# Amphenol_ICC_2.net
KiCad netlist of a schematic drawn in Altium Designer
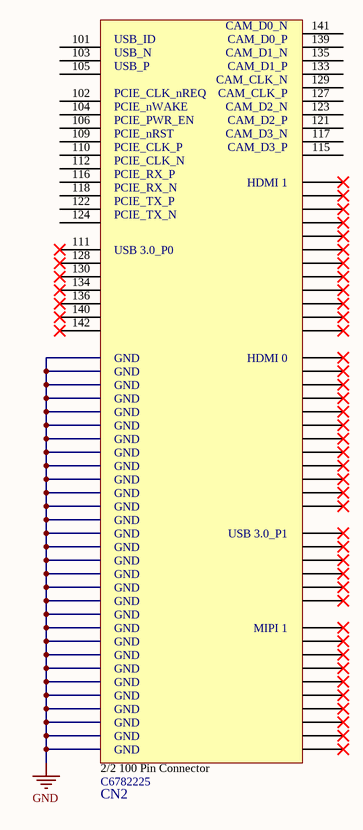
[diagram p0: Amphenol ICC_2.SchDoc]

(export (version "E")
  (design (tool "Eeschema 10.0.6"))
  (components
    (comp (ref "CN2")
      (value "2/2 100 Pin Connector")
      (footprint "CONN-SMD_100P-P0.40_10164227-1001A1RLF")
      (description "100 Position Board to Board Connector Surface Mount,P=0.4mm Gold")
      (fields (field (name "NAME") "C6782225") (field (name "SOURCE") "LCSC"))
      (libsource (lib "C6782225_Part 2") (part "10164227-1001A1RLF"))
    )
  )
  (nets
    (net (code "1") (name "GND") (class "Default")
      (node (ref "CN2") (pin "107") (pinfunction "GND_107") (pintype "passive"))
      (node (ref "CN2") (pin "108") (pinfunction "GND_108") (pintype "passive"))
      (node (ref "CN2") (pin "113") (pinfunction "GND_113") (pintype "passive"))
      (node (ref "CN2") (pin "114") (pinfunction "GND_114") (pintype "passive"))
      (node (ref "CN2") (pin "119") (pinfunction "GND_119") (pintype "passive"))
      (node (ref "CN2") (pin "120") (pinfunction "GND_120") (pintype "passive"))
      (node (ref "CN2") (pin "125") (pinfunction "GND_125") (pintype "passive"))
      (node (ref "CN2") (pin "126") (pinfunction "GND_126") (pintype "passive"))
      (node (ref "CN2") (pin "131") (pinfunction "GND_131") (pintype "passive"))
      (node (ref "CN2") (pin "132") (pinfunction "GND_132") (pintype "passive"))
      (node (ref "CN2") (pin "137") (pinfunction "GND_137") (pintype "passive"))
      (node (ref "CN2") (pin "138") (pinfunction "GND_138") (pintype "passive"))
      (node (ref "CN2") (pin "144") (pinfunction "GND_144") (pintype "passive"))
      (node (ref "CN2") (pin "150") (pinfunction "GND_150") (pintype "passive"))
      (node (ref "CN2") (pin "155") (pinfunction "GND_155") (pintype "passive"))
      (node (ref "CN2") (pin "156") (pinfunction "GND_156") (pintype "passive"))
      (node (ref "CN2") (pin "161") (pinfunction "GND_161") (pintype "passive"))
      (node (ref "CN2") (pin "162") (pinfunction "GND_162") (pintype "passive"))
      (node (ref "CN2") (pin "167") (pinfunction "GND_167") (pintype "passive"))
      (node (ref "CN2") (pin "168") (pinfunction "GND_168") (pintype "passive"))
      (node (ref "CN2") (pin "173") (pinfunction "GND_173") (pintype "passive"))
      (node (ref "CN2") (pin "174") (pinfunction "GND_174") (pintype "passive"))
      (node (ref "CN2") (pin "179") (pinfunction "GND_179") (pintype "passive"))
      (node (ref "CN2") (pin "180") (pinfunction "GND_180") (pintype "passive"))
      (node (ref "CN2") (pin "185") (pinfunction "GND_185") (pintype "passive"))
      (node (ref "CN2") (pin "186") (pinfunction "GND_186") (pintype "passive"))
      (node (ref "CN2") (pin "191") (pinfunction "GND_191") (pintype "passive"))
      (node (ref "CN2") (pin "192") (pinfunction "GND_192") (pintype "passive"))
      (node (ref "CN2") (pin "197") (pinfunction "GND_197") (pintype "passive"))
      (node (ref "CN2") (pin "198") (pinfunction "GND_198") (pintype "passive"))
    )
    (net (code "2") (name "unconnected-(CN2-MIPI_C_N-Pad127)") (class "Default")
      (node (ref "CN2") (pin "127") (pinfunction "MIPI_C_N_127") (pintype "passive"))
    )
    (net (code "3") (name "unconnected-(CN2-MIPI_C_P-Pad129)") (class "Default")
      (node (ref "CN2") (pin "129") (pinfunction "MIPI_C_P_129") (pintype "passive"))
    )
    (net (code "4") (name "unconnected-(CN2-MIPI_D0_N-Pad115)") (class "Default")
      (node (ref "CN2") (pin "115") (pinfunction "MIPI_D0_N_115") (pintype "passive"))
    )
    (net (code "5") (name "unconnected-(CN2-MIPI_D0_P-Pad117)") (class "Default")
      (node (ref "CN2") (pin "117") (pinfunction "MIPI_D0_P_117") (pintype "passive"))
    )
    (net (code "6") (name "unconnected-(CN2-MIPI_D1_N-Pad121)") (class "Default")
      (node (ref "CN2") (pin "121") (pinfunction "MIPI_D1_N_121") (pintype "passive"))
    )
    (net (code "7") (name "unconnected-(CN2-MIPI_D1_P-Pad123)") (class "Default")
      (node (ref "CN2") (pin "123") (pinfunction "MIPI_D1_P_123") (pintype "passive"))
    )
    (net (code "8") (name "unconnected-(CN2-MIPI_D2_N-Pad133)") (class "Default")
      (node (ref "CN2") (pin "133") (pinfunction "MIPI_D2_N_133") (pintype "passive"))
    )
    (net (code "9") (name "unconnected-(CN2-MIPI_D2_P-Pad135)") (class "Default")
      (node (ref "CN2") (pin "135") (pinfunction "MIPI_D2_P_135") (pintype "passive"))
    )
    (net (code "10") (name "unconnected-(CN2-MIPI_D3_N-Pad139)") (class "Default")
      (node (ref "CN2") (pin "139") (pinfunction "MIPI_D3_N_139") (pintype "passive"))
    )
    (net (code "11") (name "unconnected-(CN2-MIPI_D3_P-Pad141)") (class "Default")
      (node (ref "CN2") (pin "141") (pinfunction "MIPI_D3_P_141") (pintype "passive"))
    )
    (net (code "12") (name "unconnected-(CN2-PCIE_PWR_EN-Pad106)") (class "Default")
      (node (ref "CN2") (pin "106") (pinfunction "PCIE_PWR_EN_106") (pintype "passive"))
    )
    (net (code "13") (name "unconnected-(CN2-PCIE_RST-Pad109)") (class "Default")
      (node (ref "CN2") (pin "109") (pinfunction "PCIE_RST_109") (pintype "passive"))
    )
    (net (code "14") (name "unconnected-(CN2-PCIe_CLK_N-Pad112)") (class "Default")
      (node (ref "CN2") (pin "112") (pinfunction "PCIe_CLK_N_112") (pintype "passive"))
    )
    (net (code "15") (name "unconnected-(CN2-PCIe_CLK_P-Pad110)") (class "Default")
      (node (ref "CN2") (pin "110") (pinfunction "PCIe_CLK_P_110") (pintype "passive"))
    )
    (net (code "16") (name "unconnected-(CN2-PCIe_CLK_REQ-Pad102)") (class "Default")
      (node (ref "CN2") (pin "102") (pinfunction "PCIe_CLK_REQ_102") (pintype "passive"))
    )
    (net (code "17") (name "unconnected-(CN2-PCIe_RX_N-Pad118)") (class "Default")
      (node (ref "CN2") (pin "118") (pinfunction "PCIe_RX_N_118") (pintype "passive"))
    )
    (net (code "18") (name "unconnected-(CN2-PCIe_RX_P-Pad116)") (class "Default")
      (node (ref "CN2") (pin "116") (pinfunction "PCIe_RX_P_116") (pintype "passive"))
    )
    (net (code "19") (name "unconnected-(CN2-PCIe_TX_N-Pad124)") (class "Default")
      (node (ref "CN2") (pin "124") (pinfunction "PCIe_TX_N_124") (pintype "passive"))
    )
    (net (code "20") (name "unconnected-(CN2-PCIe_TX_P-Pad122)") (class "Default")
      (node (ref "CN2") (pin "122") (pinfunction "PCIe_TX_P_122") (pintype "passive"))
    )
    (net (code "21") (name "unconnected-(CN2-PCIe_WAKE-Pad104)") (class "Default")
      (node (ref "CN2") (pin "104") (pinfunction "PCIe_WAKE_104") (pintype "passive"))
    )
    (net (code "22") (name "unconnected-(CN2-Pad111)") (class "Default")
      (node (ref "CN2") (pin "111") (pinfunction "111_111") (pintype "passive"))
    )
    (net (code "23") (name "unconnected-(CN2-Pad128)") (class "Default")
      (node (ref "CN2") (pin "128") (pinfunction "128_128") (pintype "passive"))
    )
    (net (code "24") (name "unconnected-(CN2-Pad130)") (class "Default")
      (node (ref "CN2") (pin "130") (pinfunction "130_130") (pintype "passive"))
    )
    (net (code "25") (name "unconnected-(CN2-Pad134)") (class "Default")
      (node (ref "CN2") (pin "134") (pinfunction "134_134") (pintype "passive"))
    )
    (net (code "26") (name "unconnected-(CN2-Pad136)") (class "Default")
      (node (ref "CN2") (pin "136") (pinfunction "136_136") (pintype "passive"))
    )
    (net (code "27") (name "unconnected-(CN2-Pad140)") (class "Default")
      (node (ref "CN2") (pin "140") (pinfunction "140_140") (pintype "passive"))
    )
    (net (code "28") (name "unconnected-(CN2-Pad142)") (class "Default")
      (node (ref "CN2") (pin "142") (pinfunction "142_142") (pintype "passive"))
    )
    (net (code "29") (name "unconnected-(CN2-Pad143)") (class "Default")
      (node (ref "CN2") (pin "143") (pinfunction "143_143") (pintype "passive"))
    )
    (net (code "30") (name "unconnected-(CN2-Pad145)") (class "Default")
      (node (ref "CN2") (pin "145") (pinfunction "145_145") (pintype "passive"))
    )
    (net (code "31") (name "unconnected-(CN2-Pad146)") (class "Default")
      (node (ref "CN2") (pin "146") (pinfunction "146_146") (pintype "passive"))
    )
    (net (code "32") (name "unconnected-(CN2-Pad147)") (class "Default")
      (node (ref "CN2") (pin "147") (pinfunction "147_147") (pintype "passive"))
    )
    (net (code "33") (name "unconnected-(CN2-Pad148)") (class "Default")
      (node (ref "CN2") (pin "148") (pinfunction "148_148") (pintype "passive"))
    )
    (net (code "34") (name "unconnected-(CN2-Pad149)") (class "Default")
      (node (ref "CN2") (pin "149") (pinfunction "149_149") (pintype "passive"))
    )
    (net (code "35") (name "unconnected-(CN2-Pad151)") (class "Default")
      (node (ref "CN2") (pin "151") (pinfunction "151_151") (pintype "passive"))
    )
    (net (code "36") (name "unconnected-(CN2-Pad152)") (class "Default")
      (node (ref "CN2") (pin "152") (pinfunction "152_152") (pintype "passive"))
    )
    (net (code "37") (name "unconnected-(CN2-Pad153)") (class "Default")
      (node (ref "CN2") (pin "153") (pinfunction "153_153") (pintype "passive"))
    )
    (net (code "38") (name "unconnected-(CN2-Pad154)") (class "Default")
      (node (ref "CN2") (pin "154") (pinfunction "154_154") (pintype "passive"))
    )
    (net (code "39") (name "unconnected-(CN2-Pad157)") (class "Default")
      (node (ref "CN2") (pin "157") (pinfunction "157_157") (pintype "passive"))
    )
    (net (code "40") (name "unconnected-(CN2-Pad158)") (class "Default")
      (node (ref "CN2") (pin "158") (pinfunction "158_158") (pintype "passive"))
    )
    (net (code "41") (name "unconnected-(CN2-Pad159)") (class "Default")
      (node (ref "CN2") (pin "159") (pinfunction "159_159") (pintype "passive"))
    )
    (net (code "42") (name "unconnected-(CN2-Pad160)") (class "Default")
      (node (ref "CN2") (pin "160") (pinfunction "160_160") (pintype "passive"))
    )
    (net (code "43") (name "unconnected-(CN2-Pad163)") (class "Default")
      (node (ref "CN2") (pin "163") (pinfunction "163_163") (pintype "passive"))
    )
    (net (code "44") (name "unconnected-(CN2-Pad164)") (class "Default")
      (node (ref "CN2") (pin "164") (pinfunction "164_164") (pintype "passive"))
    )
    (net (code "45") (name "unconnected-(CN2-Pad165)") (class "Default")
      (node (ref "CN2") (pin "165") (pinfunction "165_165") (pintype "passive"))
    )
    (net (code "46") (name "unconnected-(CN2-Pad166)") (class "Default")
      (node (ref "CN2") (pin "166") (pinfunction "166_166") (pintype "passive"))
    )
    (net (code "47") (name "unconnected-(CN2-Pad169)") (class "Default")
      (node (ref "CN2") (pin "169") (pinfunction "169_169") (pintype "passive"))
    )
    (net (code "48") (name "unconnected-(CN2-Pad170)") (class "Default")
      (node (ref "CN2") (pin "170") (pinfunction "170_170") (pintype "passive"))
    )
    (net (code "49") (name "unconnected-(CN2-Pad171)") (class "Default")
      (node (ref "CN2") (pin "171") (pinfunction "171_171") (pintype "passive"))
    )
    (net (code "50") (name "unconnected-(CN2-Pad172)") (class "Default")
      (node (ref "CN2") (pin "172") (pinfunction "172_172") (pintype "passive"))
    )
    (net (code "51") (name "unconnected-(CN2-Pad175)") (class "Default")
      (node (ref "CN2") (pin "175") (pinfunction "175_175") (pintype "passive"))
    )
    (net (code "52") (name "unconnected-(CN2-Pad176)") (class "Default")
      (node (ref "CN2") (pin "176") (pinfunction "176_176") (pintype "passive"))
    )
    (net (code "53") (name "unconnected-(CN2-Pad177)") (class "Default")
      (node (ref "CN2") (pin "177") (pinfunction "177_177") (pintype "passive"))
    )
    (net (code "54") (name "unconnected-(CN2-Pad178)") (class "Default")
      (node (ref "CN2") (pin "178") (pinfunction "178_178") (pintype "passive"))
    )
    (net (code "55") (name "unconnected-(CN2-Pad181)") (class "Default")
      (node (ref "CN2") (pin "181") (pinfunction "181_181") (pintype "passive"))
    )
    (net (code "56") (name "unconnected-(CN2-Pad182)") (class "Default")
      (node (ref "CN2") (pin "182") (pinfunction "182_182") (pintype "passive"))
    )
    (net (code "57") (name "unconnected-(CN2-Pad183)") (class "Default")
      (node (ref "CN2") (pin "183") (pinfunction "183_183") (pintype "passive"))
    )
    (net (code "58") (name "unconnected-(CN2-Pad184)") (class "Default")
      (node (ref "CN2") (pin "184") (pinfunction "184_184") (pintype "passive"))
    )
    (net (code "59") (name "unconnected-(CN2-Pad187)") (class "Default")
      (node (ref "CN2") (pin "187") (pinfunction "187_187") (pintype "passive"))
    )
    (net (code "60") (name "unconnected-(CN2-Pad188)") (class "Default")
      (node (ref "CN2") (pin "188") (pinfunction "188_188") (pintype "passive"))
    )
    (net (code "61") (name "unconnected-(CN2-Pad189)") (class "Default")
      (node (ref "CN2") (pin "189") (pinfunction "189_189") (pintype "passive"))
    )
    (net (code "62") (name "unconnected-(CN2-Pad190)") (class "Default")
      (node (ref "CN2") (pin "190") (pinfunction "190_190") (pintype "passive"))
    )
    (net (code "63") (name "unconnected-(CN2-Pad193)") (class "Default")
      (node (ref "CN2") (pin "193") (pinfunction "193_193") (pintype "passive"))
    )
    (net (code "64") (name "unconnected-(CN2-Pad194)") (class "Default")
      (node (ref "CN2") (pin "194") (pinfunction "194_194") (pintype "passive"))
    )
    (net (code "65") (name "unconnected-(CN2-Pad195)") (class "Default")
      (node (ref "CN2") (pin "195") (pinfunction "195_195") (pintype "passive"))
    )
    (net (code "66") (name "unconnected-(CN2-Pad196)") (class "Default")
      (node (ref "CN2") (pin "196") (pinfunction "196_196") (pintype "passive"))
    )
    (net (code "67") (name "unconnected-(CN2-Pad199)") (class "Default")
      (node (ref "CN2") (pin "199") (pinfunction "199_199") (pintype "passive"))
    )
    (net (code "68") (name "unconnected-(CN2-Pad200)") (class "Default")
      (node (ref "CN2") (pin "200") (pinfunction "200_200") (pintype "passive"))
    )
    (net (code "69") (name "unconnected-(CN2-USB_ID-Pad101)") (class "Default")
      (node (ref "CN2") (pin "101") (pinfunction "USB_ID_101") (pintype "passive"))
    )
    (net (code "70") (name "unconnected-(CN2-USB_N-Pad103)") (class "Default")
      (node (ref "CN2") (pin "103") (pinfunction "USB_N_103") (pintype "passive"))
    )
    (net (code "71") (name "unconnected-(CN2-USB_P-Pad105)") (class "Default")
      (node (ref "CN2") (pin "105") (pinfunction "USB_P_105") (pintype "passive"))
    )
  )
)
